# MicroController.net
KiCad netlist of a schematic drawn in Altium Designer
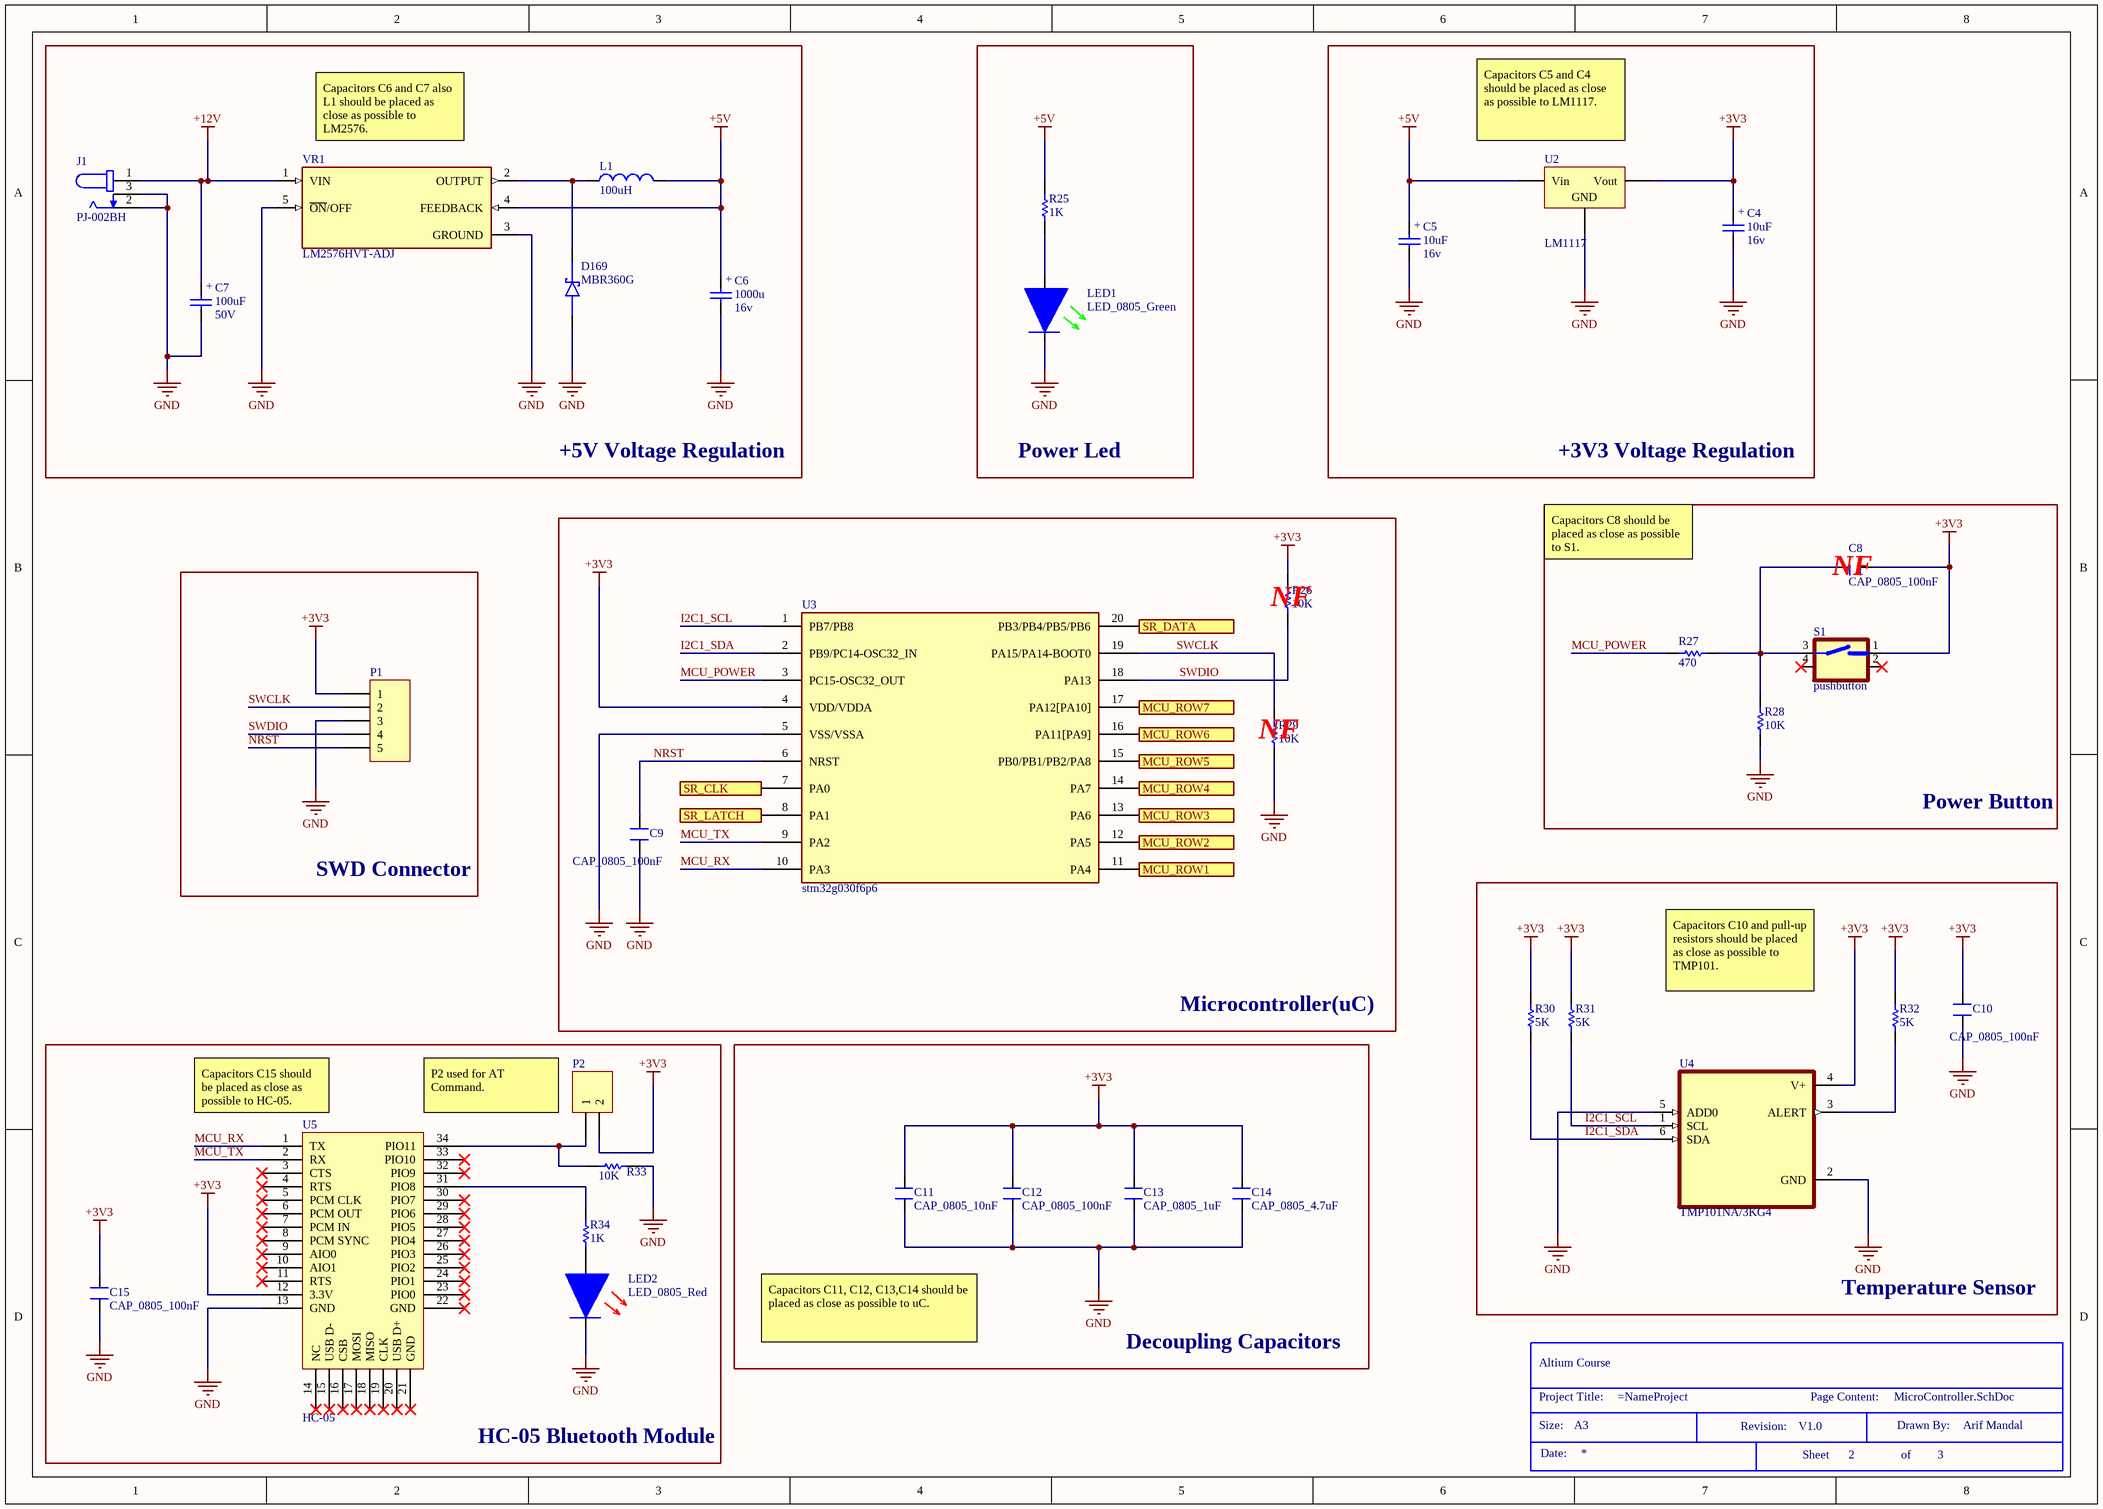
[diagram p0: MicroController.SchDoc]

(export (version "E")
  (design (tool "Eeschema 10.0.6"))
  (components
    (comp (ref "*")
      (value "Title Block")
      (fields (field (name "SIZE") "A3") (field (name "DRAWN BY") "Arif Mandal"))
      (libsource (lib "Bluetooth_Controlled_Led_Matrix_Design") (part "Title Block"))
    )
    (comp (ref "C4")
      (value "10uF")
      (footprint "MY_SMC_B")
      (description "Polar capacitor")
      (fields (field (name "ASID PART NUMBER") "C-AS") (field (name "VOLTE") "16v"))
      (libsource (lib "Mylib") (part "Cap Pol"))
    )
    (comp (ref "C5")
      (value "10uF")
      (footprint "MY_SMC_B")
      (description "Polar capacitor")
      (fields (field (name "ASID PART NUMBER") "C-AS") (field (name "VOLTE") "16v"))
      (libsource (lib "Mylib") (part "Cap Pol"))
    )
    (comp (ref "C6")
      (value "1000u")
      (footprint "MY_CLV_0810")
      (description "Polar capacitor")
      (fields (field (name "ASID PART NUMBER") "C-AS") (field (name "VOLTE") "16v"))
      (libsource (lib "Mylib") (part "Cap Pol"))
    )
    (comp (ref "C7")
      (value "100uF")
      (footprint "MY_CLV_0810")
      (description "Polar capacitor")
      (fields (field (name "ASID PART NUMBER") "C-AS") (field (name "VOLTE") "50V"))
      (libsource (lib "Mylib") (part "Cap Pol"))
    )
    (comp (ref "C8")
      (value "CAP_0805_100nF")
      (footprint "CAP_0805")
      (description "0805 100nF 16VDC ±10% X7R")
      (fields (field (name "TOLERANCE") "%10"))
      (libsource (lib "I2C_Shield") (part "CAP_0805_100nF"))
    )
    (comp (ref "C9")
      (value "CAP_0805_100nF")
      (footprint "CAP_0805")
      (description "0805 100nF 16VDC ±10% X7R")
      (fields (field (name "TOLERANCE") "%10"))
      (libsource (lib "I2C_Shield") (part "CAP_0805_100nF"))
    )
    (comp (ref "C10")
      (value "CAP_0805_100nF")
      (footprint "CAP_0805")
      (description "0805 100nF 16VDC ±10% X7R")
      (fields (field (name "TOLERANCE") "%10"))
      (libsource (lib "I2C_Shield") (part "CAP_0805_100nF"))
    )
    (comp (ref "C11")
      (value "CAP_0805_10nF")
      (footprint "CAP_0805")
      (description "0805 10nF 16VDC ±10% X7R")
      (fields (field (name "TOLERANCE") "%10"))
      (libsource (lib "Bluetooth_Controlled_Led_Matrix_Design") (part "CAP_0805_10nF"))
    )
    (comp (ref "C12")
      (value "CAP_0805_100nF")
      (footprint "CAP_0805")
      (description "0805 100nF 16VDC ±10% X7R")
      (fields (field (name "TOLERANCE") "%10"))
      (libsource (lib "I2C_Shield") (part "CAP_0805_100nF"))
    )
    (comp (ref "C13")
      (value "CAP_0805_1uF")
      (footprint "CAP_0805")
      (description "0805 1uF 16VDC ±10% X7R")
      (fields (field (name "TOLERANCE") "%10"))
      (libsource (lib "Bluetooth_Controlled_Led_Matrix_Design") (part "CAP_0805_1uF"))
    )
    (comp (ref "C14")
      (value "CAP_0805_4.7uF")
      (footprint "CAP_0805")
      (description "0805 4.7uF 16VDC ±10% X7R")
      (fields (field (name "TOLERANCE") "%10"))
      (libsource (lib "Bluetooth_Controlled_Led_Matrix_Design") (part "CAP_0805_4.7uF"))
    )
    (comp (ref "C15")
      (value "CAP_0805_100nF")
      (footprint "CAP_0805")
      (description "0805 100nF 16VDC ±10% X7R")
      (fields (field (name "TOLERANCE") "%10"))
      (libsource (lib "I2C_Shield") (part "CAP_0805_100nF"))
    )
    (comp (ref "D169")
      (value "MBR360G")
      (footprint "DIOAD950W125L840D505")
      (description "Diode Schottky 60V 3A Through Hole DO-201AD")
      (fields (field (name "MF") "ON Semiconductor"))
      (libsource (lib "Bluetooth_Controlled_Led_Matrix_Design") (part "MBR360G"))
    )
    (comp (ref "J1")
      (value "PJ-002BH")
      (footprint "CUI_PJ-002BH")
      (description "2.5 x 6.5 mm, 5.0 A, Horizontal, Through Hole, Dc Power Jack Connector")
      (fields (field (name "MF") "CUI Devices"))
      (libsource (lib "Bluetooth_Controlled_Led_Matrix_Design") (part "PJ-002BH"))
    )
    (comp (ref "L1")
      (value "100uH")
      (footprint "MY_DR125")
      (description "Inductor")
      (fields (field (name "ASID PART NUMBER") "Inductor-AS"))
      (libsource (lib "Mylib") (part "Inductor"))
    )
    (comp (ref "LED1")
      (value "LED_0805_Green")
      (footprint "LED_0805")
      (description "LED SMD 0805 GREEN 550mcd")
      (libsource (lib "I2C_Shield") (part "LED_0805_Green"))
    )
    (comp (ref "LED2")
      (value "LED_0805_Red")
      (footprint "LED_0805")
      (description "LED SMD 0805 RED 550mcd")
      (libsource (lib "I2C_Shield") (part "LED_0805_Red"))
    )
    (comp (ref "P1")
      (value "Header 5")
      (footprint "My_1X05")
      (description "Header, 5-Pin")
      (fields (field (name "ASID PART NUMBER") "Header 5-AS"))
      (libsource (lib "Mylib") (part "Header 5"))
    )
    (comp (ref "P2")
      (value "Header 2")
      (footprint "My_1X02")
      (description "Header, 2-Pin")
      (fields (field (name "ASID PART NUMBER") "Header 2-AS"))
      (libsource (lib "Mylib") (part "Header 2"))
    )
    (comp (ref "R25")
      (value "1K")
      (footprint "MY_0805")
      (description "Standard resistor")
      (fields (field (name "ASID PART NUMBER") "Res-AS"))
      (libsource (lib "Mylib") (part "Res"))
    )
    (comp (ref "R26")
      (value "10K")
      (footprint "MY_0805")
      (description "Standard resistor")
      (fields (field (name "ASID PART NUMBER") "Res-AS"))
      (libsource (lib "Mylib") (part "Res"))
    )
    (comp (ref "R27")
      (value "470")
      (footprint "MY_0805")
      (description "Standard resistor")
      (fields (field (name "ASID PART NUMBER") "Res-AS"))
      (libsource (lib "Mylib") (part "Res"))
    )
    (comp (ref "R28")
      (value "10K")
      (footprint "MY_0805")
      (description "Standard resistor")
      (fields (field (name "ASID PART NUMBER") "Res-AS"))
      (libsource (lib "Mylib") (part "Res"))
    )
    (comp (ref "R29")
      (value "10K")
      (footprint "MY_0805")
      (description "Standard resistor")
      (fields (field (name "ASID PART NUMBER") "Res-AS"))
      (libsource (lib "Mylib") (part "Res"))
    )
    (comp (ref "R30")
      (value "5K")
      (footprint "MY_0805")
      (description "Standard resistor")
      (fields (field (name "ASID PART NUMBER") "Res-AS"))
      (libsource (lib "Mylib") (part "Res"))
    )
    (comp (ref "R31")
      (value "5K")
      (footprint "MY_0805")
      (description "Standard resistor")
      (fields (field (name "ASID PART NUMBER") "Res-AS"))
      (libsource (lib "Mylib") (part "Res"))
    )
    (comp (ref "R32")
      (value "5K")
      (footprint "MY_0805")
      (description "Standard resistor")
      (fields (field (name "ASID PART NUMBER") "Res-AS"))
      (libsource (lib "Mylib") (part "Res"))
    )
    (comp (ref "R33")
      (value "10K")
      (footprint "MY_0805")
      (description "Standard resistor")
      (fields (field (name "ASID PART NUMBER") "Res-AS"))
      (libsource (lib "Mylib") (part "Res"))
    )
    (comp (ref "R34")
      (value "1K")
      (footprint "MY_0805")
      (description "Standard resistor")
      (fields (field (name "ASID PART NUMBER") "Res-AS"))
      (libsource (lib "Mylib") (part "Res"))
    )
    (comp (ref "S1")
      (value "pushbutton")
      (footprint "button")
      (libsource (lib "Bluetooth_Controlled_Led_Matrix_Design") (part "pushbutton"))
    )
    (comp (ref "U2")
      (value "LM1117")
      (footprint "MY_SOT223")
      (description "Low Drop Voltage Reg")
      (fields (field (name "ASID PART NUMBER") "LM1117-AS"))
      (libsource (lib "Mylib") (part "LM1117"))
    )
    (comp (ref "U3")
      (value "stm32g030f6p6")
      (footprint "TSSOP20")
      (description "ARM® Cortex®-M0+ STM32G0 Microcontroller IC 32-Bit Single-Core 64MHz 32KB (32K x 8) FLASH 20-TSSOP")
      (libsource (lib "Bluetooth_Controlled_Led_Matrix_Design") (part "stm32g030f6p6"))
    )
    (comp (ref "U4")
      (value "TMP101NA/3KG4")
      (footprint "SOT95P280X145-6N")
      (libsource (lib "Bluetooth_Controlled_Led_Matrix_Design") (part "TMP101NA/3KG4"))
    )
    (comp (ref "U5")
      (value "HC-05")
      (footprint "HC-05")
      (libsource (lib "Bluetooth_Controlled_Led_Matrix_Design") (part "HC-05"))
    )
    (comp (ref "VR1")
      (value "LM2576HVT-ADJ")
      (footprint "TO170P1067X483X1651-5")
      (description "SIMPLE SWITCHER&reg; 4V to 60V, 3A Low Component Count Step-Down Regulator 5-TO-220 -40 to 125")
      (fields (field (name "MF") "Texas Instruments"))
      (libsource (lib "Bluetooth_Controlled_Led_Matrix_Design") (part "LM2576HVT-ADJ"))
    )
  )
  (nets
    (net (code "1") (name "+3V3") (class "Default")
      (node (ref "C10") (pin "2") (pinfunction "2_2") (pintype "passive"))
      (node (ref "C11") (pin "2") (pinfunction "2_2") (pintype "passive"))
      (node (ref "C12") (pin "2") (pinfunction "2_2") (pintype "passive"))
      (node (ref "C13") (pin "2") (pinfunction "2_2") (pintype "passive"))
      (node (ref "C14") (pin "2") (pinfunction "2_2") (pintype "passive"))
      (node (ref "C15") (pin "2") (pinfunction "2_2") (pintype "passive"))
      (node (ref "C4") (pin "+") (pinfunction "+_+") (pintype "passive"))
      (node (ref "C8") (pin "2") (pinfunction "2_2") (pintype "passive"))
      (node (ref "P1") (pin "1") (pinfunction "1_1") (pintype "passive"))
      (node (ref "P2") (pin "2") (pinfunction "2_2") (pintype "passive"))
      (node (ref "R26") (pin "1") (pinfunction "1_1") (pintype "passive"))
      (node (ref "R30") (pin "1") (pinfunction "1_1") (pintype "passive"))
      (node (ref "R31") (pin "1") (pinfunction "1_1") (pintype "passive"))
      (node (ref "R32") (pin "1") (pinfunction "1_1") (pintype "passive"))
      (node (ref "S1") (pin "1") (pinfunction "2_1") (pintype "passive"))
      (node (ref "U2") (pin "2") (pinfunction "Vout_2") (pintype "passive"))
      (node (ref "U3") (pin "4") (pinfunction "VDD/VDDA_4") (pintype "passive"))
      (node (ref "U4") (pin "4") (pinfunction "V+_4") (pintype "power_in"))
      (node (ref "U5") (pin "12") (pinfunction "3.3V_12") (pintype "passive"))
    )
    (net (code "2") (name "+5V") (class "Default")
      (node (ref "C5") (pin "+") (pinfunction "+_+") (pintype "passive"))
      (node (ref "C6") (pin "+") (pinfunction "+_+") (pintype "passive"))
      (node (ref "L1") (pin "2") (pinfunction "2_2") (pintype "passive"))
      (node (ref "R25") (pin "2") (pinfunction "2_2") (pintype "passive"))
      (node (ref "U2") (pin "3") (pinfunction "Vin_3") (pintype "passive"))
      (node (ref "VR1") (pin "4") (pinfunction "FEEDBACK_4") (pintype "input"))
    )
    (net (code "3") (name "+12V") (class "Default")
      (node (ref "C7") (pin "+") (pinfunction "+_+") (pintype "passive"))
      (node (ref "J1") (pin "1") (pinfunction "1_1") (pintype "passive"))
      (node (ref "VR1") (pin "1") (pinfunction "VIN_1") (pintype "input"))
    )
    (net (code "4") (name "/I2C1_SCL") (class "Default")
      (node (ref "R31") (pin "2") (pinfunction "2_2") (pintype "passive"))
      (node (ref "U3") (pin "1") (pinfunction "PB7/PB8_1") (pintype "passive"))
      (node (ref "U4") (pin "1") (pinfunction "SCL_1") (pintype "input"))
    )
    (net (code "5") (name "/I2C1_SDA") (class "Default")
      (node (ref "R30") (pin "2") (pinfunction "2_2") (pintype "passive"))
      (node (ref "U3") (pin "2") (pinfunction "PB9/PC14-OSC32_IN_2") (pintype "passive"))
      (node (ref "U4") (pin "6") (pinfunction "SDA_6") (pintype "input"))
    )
    (net (code "6") (name "/MCU_POWER") (class "Default")
      (node (ref "R27") (pin "1") (pinfunction "1_1") (pintype "passive"))
      (node (ref "U3") (pin "3") (pinfunction "PC15-OSC32_OUT_3") (pintype "passive"))
    )
    (net (code "7") (name "/MCU_ROW1") (class "Default")
      (node (ref "U3") (pin "11") (pinfunction "PA4_11") (pintype "passive"))
    )
    (net (code "8") (name "/MCU_ROW2") (class "Default")
      (node (ref "U3") (pin "12") (pinfunction "PA5_12") (pintype "passive"))
    )
    (net (code "9") (name "/MCU_ROW3") (class "Default")
      (node (ref "U3") (pin "13") (pinfunction "PA6_13") (pintype "passive"))
    )
    (net (code "10") (name "/MCU_ROW4") (class "Default")
      (node (ref "U3") (pin "14") (pinfunction "PA7_14") (pintype "passive"))
    )
    (net (code "11") (name "/MCU_ROW5") (class "Default")
      (node (ref "U3") (pin "15") (pinfunction "PB0/PB1/PB2/PA8_15") (pintype "passive"))
    )
    (net (code "12") (name "/MCU_ROW6") (class "Default")
      (node (ref "U3") (pin "16") (pinfunction "PA11[PA9]_16") (pintype "passive"))
    )
    (net (code "13") (name "/MCU_ROW7") (class "Default")
      (node (ref "U3") (pin "17") (pinfunction "PA12[PA10]_17") (pintype "passive"))
    )
    (net (code "14") (name "/MCU_RX") (class "Default")
      (node (ref "U3") (pin "10") (pinfunction "PA3_10") (pintype "passive"))
      (node (ref "U5") (pin "1") (pinfunction "TX_1") (pintype "passive"))
    )
    (net (code "15") (name "/MCU_TX") (class "Default")
      (node (ref "U3") (pin "9") (pinfunction "PA2_9") (pintype "passive"))
      (node (ref "U5") (pin "2") (pinfunction "RX_2") (pintype "passive"))
    )
    (net (code "16") (name "/NRST") (class "Default")
      (node (ref "C9") (pin "2") (pinfunction "2_2") (pintype "passive"))
      (node (ref "P1") (pin "5") (pinfunction "5_5") (pintype "passive"))
      (node (ref "U3") (pin "6") (pinfunction "NRST_6") (pintype "passive"))
    )
    (net (code "17") (name "/SR_CLK") (class "Default")
      (node (ref "U3") (pin "7") (pinfunction "PA0_7") (pintype "passive"))
    )
    (net (code "18") (name "/SR_DATA") (class "Default")
      (node (ref "U3") (pin "20") (pinfunction "PB3/PB4/PB5/PB6_20") (pintype "passive"))
    )
    (net (code "19") (name "/SR_LATCH") (class "Default")
      (node (ref "U3") (pin "8") (pinfunction "PA1_8") (pintype "passive"))
    )
    (net (code "20") (name "/SWCLK") (class "Default")
      (node (ref "P1") (pin "2") (pinfunction "2_2") (pintype "passive"))
      (node (ref "R29") (pin "1") (pinfunction "1_1") (pintype "passive"))
      (node (ref "U3") (pin "19") (pinfunction "PA15/PA14-BOOT0_19") (pintype "passive"))
    )
    (net (code "21") (name "/SWDIO") (class "Default")
      (node (ref "P1") (pin "4") (pinfunction "4_4") (pintype "passive"))
      (node (ref "R26") (pin "2") (pinfunction "2_2") (pintype "passive"))
      (node (ref "U3") (pin "18") (pinfunction "PA13_18") (pintype "passive"))
    )
    (net (code "22") (name "GND") (class "Default")
      (node (ref "C10") (pin "1") (pinfunction "1_1") (pintype "passive"))
      (node (ref "C11") (pin "1") (pinfunction "1_1") (pintype "passive"))
      (node (ref "C12") (pin "1") (pinfunction "1_1") (pintype "passive"))
      (node (ref "C13") (pin "1") (pinfunction "1_1") (pintype "passive"))
      (node (ref "C14") (pin "1") (pinfunction "1_1") (pintype "passive"))
      (node (ref "C15") (pin "1") (pinfunction "1_1") (pintype "passive"))
      (node (ref "C4") (pin "-") (pinfunction "-_-") (pintype "passive"))
      (node (ref "C5") (pin "-") (pinfunction "-_-") (pintype "passive"))
      (node (ref "C6") (pin "-") (pinfunction "-_-") (pintype "passive"))
      (node (ref "C7") (pin "-") (pinfunction "-_-") (pintype "passive"))
      (node (ref "C9") (pin "1") (pinfunction "1_1") (pintype "passive"))
      (node (ref "D169") (pin "A") (pinfunction "A_A") (pintype "passive"))
      (node (ref "J1") (pin "2") (pinfunction "2_2") (pintype "passive"))
      (node (ref "J1") (pin "3") (pinfunction "3_3") (pintype "passive"))
      (node (ref "LED1") (pin "C") (pinfunction "C_C") (pintype "passive"))
      (node (ref "LED2") (pin "C") (pinfunction "C_C") (pintype "passive"))
      (node (ref "P1") (pin "3") (pinfunction "3_3") (pintype "passive"))
      (node (ref "R28") (pin "2") (pinfunction "2_2") (pintype "passive"))
      (node (ref "R29") (pin "2") (pinfunction "2_2") (pintype "passive"))
      (node (ref "R33") (pin "1") (pinfunction "1_1") (pintype "passive"))
      (node (ref "U2") (pin "1") (pinfunction "GND_1") (pintype "passive"))
      (node (ref "U3") (pin "5") (pinfunction "VSS/VSSA_5") (pintype "passive"))
      (node (ref "U4") (pin "2") (pinfunction "GND_2") (pintype "power_in"))
      (node (ref "U4") (pin "5") (pinfunction "ADD0_5") (pintype "input"))
      (node (ref "U5") (pin "13") (pinfunction "GND_13") (pintype "passive"))
      (node (ref "VR1") (pin "3") (pinfunction "GROUND_3") (pintype "power_in"))
      (node (ref "VR1") (pin "5") (pinfunction "~{ON}/OFF_5") (pintype "input"))
    )
    (net (code "23") (name "Net-(C8-Pad1)") (class "Default")
      (node (ref "C8") (pin "1") (pinfunction "1_1") (pintype "passive"))
      (node (ref "R27") (pin "2") (pinfunction "2_2") (pintype "passive"))
      (node (ref "R28") (pin "1") (pinfunction "1_1") (pintype "passive"))
      (node (ref "S1") (pin "3") (pinfunction "1_3") (pintype "passive"))
    )
    (net (code "24") (name "Net-(LED1-PadA)") (class "Default")
      (node (ref "LED1") (pin "A") (pinfunction "A_A") (pintype "passive"))
      (node (ref "R25") (pin "1") (pinfunction "1_1") (pintype "passive"))
    )
    (net (code "25") (name "Net-(LED2-PadA)") (class "Default")
      (node (ref "LED2") (pin "A") (pinfunction "A_A") (pintype "passive"))
      (node (ref "R34") (pin "1") (pinfunction "1_1") (pintype "passive"))
    )
    (net (code "26") (name "Net-(U4-ALERT)") (class "Default")
      (node (ref "R32") (pin "2") (pinfunction "2_2") (pintype "passive"))
      (node (ref "U4") (pin "3") (pinfunction "ALERT_3") (pintype "output"))
    )
    (net (code "27") (name "Net-(U5-PIO8)") (class "Default")
      (node (ref "R34") (pin "2") (pinfunction "2_2") (pintype "passive"))
      (node (ref "U5") (pin "31") (pinfunction "PIO8_31") (pintype "passive"))
    )
    (net (code "28") (name "Net-(U5-PIO11)") (class "Default")
      (node (ref "P2") (pin "1") (pinfunction "1_1") (pintype "passive"))
      (node (ref "R33") (pin "2") (pinfunction "2_2") (pintype "passive"))
      (node (ref "U5") (pin "34") (pinfunction "PIO11_34") (pintype "passive"))
    )
    (net (code "29") (name "Net-(VR1-OUTPUT)") (class "Default")
      (node (ref "D169") (pin "C") (pinfunction "C_C") (pintype "passive"))
      (node (ref "L1") (pin "1") (pinfunction "1_1") (pintype "passive"))
      (node (ref "VR1") (pin "2") (pinfunction "OUTPUT_2") (pintype "output"))
    )
    (net (code "30") (name "unconnected-(S1-1-Pad4)") (class "Default")
      (node (ref "S1") (pin "4") (pinfunction "1_4") (pintype "passive+no_connect"))
    )
    (net (code "31") (name "unconnected-(S1-Pad2)") (class "Default")
      (node (ref "S1") (pin "2") (pinfunction "2_2") (pintype "passive+no_connect"))
    )
    (net (code "32") (name "unconnected-(U5-AIO0-Pad9)") (class "Default")
      (node (ref "U5") (pin "9") (pinfunction "AIO0_9") (pintype "passive+no_connect"))
    )
    (net (code "33") (name "unconnected-(U5-AIO1-Pad10)") (class "Default")
      (node (ref "U5") (pin "10") (pinfunction "AIO1_10") (pintype "passive+no_connect"))
    )
    (net (code "34") (name "unconnected-(U5-CLK-Pad19)") (class "Default")
      (node (ref "U5") (pin "19") (pinfunction "CLK_19") (pintype "passive+no_connect"))
    )
    (net (code "35") (name "unconnected-(U5-CSB-Pad16)") (class "Default")
      (node (ref "U5") (pin "16") (pinfunction "CSB_16") (pintype "passive+no_connect"))
    )
    (net (code "36") (name "unconnected-(U5-CTS-Pad3)") (class "Default")
      (node (ref "U5") (pin "3") (pinfunction "CTS_3") (pintype "passive+no_connect"))
    )
    (net (code "37") (name "unconnected-(U5-GND-Pad21)") (class "Default")
      (node (ref "U5") (pin "21") (pinfunction "GND_21") (pintype "passive+no_connect"))
    )
    (net (code "38") (name "unconnected-(U5-GND-Pad22)") (class "Default")
      (node (ref "U5") (pin "22") (pinfunction "GND_22") (pintype "passive+no_connect"))
    )
    (net (code "39") (name "unconnected-(U5-MISO-Pad18)") (class "Default")
      (node (ref "U5") (pin "18") (pinfunction "MISO_18") (pintype "passive+no_connect"))
    )
    (net (code "40") (name "unconnected-(U5-MOSI-Pad17)") (class "Default")
      (node (ref "U5") (pin "17") (pinfunction "MOSI_17") (pintype "passive+no_connect"))
    )
    (net (code "41") (name "unconnected-(U5-NC-Pad14)") (class "Default")
      (node (ref "U5") (pin "14") (pinfunction "NC_14") (pintype "passive+no_connect"))
    )
    (net (code "42") (name "unconnected-(U5-PCM_CLK-Pad5)") (class "Default")
      (node (ref "U5") (pin "5") (pinfunction "PCM_CLK_5") (pintype "passive+no_connect"))
    )
    (net (code "43") (name "unconnected-(U5-PCM_IN-Pad7)") (class "Default")
      (node (ref "U5") (pin "7") (pinfunction "PCM_IN_7") (pintype "passive+no_connect"))
    )
    (net (code "44") (name "unconnected-(U5-PCM_OUT-Pad6)") (class "Default")
      (node (ref "U5") (pin "6") (pinfunction "PCM_OUT_6") (pintype "passive+no_connect"))
    )
    (net (code "45") (name "unconnected-(U5-PCM_SYNC-Pad8)") (class "Default")
      (node (ref "U5") (pin "8") (pinfunction "PCM_SYNC_8") (pintype "passive+no_connect"))
    )
    (net (code "46") (name "unconnected-(U5-PIO0-Pad23)") (class "Default")
      (node (ref "U5") (pin "23") (pinfunction "PIO0_23") (pintype "passive+no_connect"))
    )
    (net (code "47") (name "unconnected-(U5-PIO1-Pad24)") (class "Default")
      (node (ref "U5") (pin "24") (pinfunction "PIO1_24") (pintype "passive+no_connect"))
    )
    (net (code "48") (name "unconnected-(U5-PIO2-Pad25)") (class "Default")
      (node (ref "U5") (pin "25") (pinfunction "PIO2_25") (pintype "passive+no_connect"))
    )
    (net (code "49") (name "unconnected-(U5-PIO3-Pad26)") (class "Default")
      (node (ref "U5") (pin "26") (pinfunction "PIO3_26") (pintype "passive+no_connect"))
    )
    (net (code "50") (name "unconnected-(U5-PIO4-Pad27)") (class "Default")
      (node (ref "U5") (pin "27") (pinfunction "PIO4_27") (pintype "passive+no_connect"))
    )
    (net (code "51") (name "unconnected-(U5-PIO5-Pad28)") (class "Default")
      (node (ref "U5") (pin "28") (pinfunction "PIO5_28") (pintype "passive+no_connect"))
    )
    (net (code "52") (name "unconnected-(U5-PIO6-Pad29)") (class "Default")
      (node (ref "U5") (pin "29") (pinfunction "PIO6_29") (pintype "passive+no_connect"))
    )
    (net (code "53") (name "unconnected-(U5-PIO7-Pad30)") (class "Default")
      (node (ref "U5") (pin "30") (pinfunction "PIO7_30") (pintype "passive+no_connect"))
    )
    (net (code "54") (name "unconnected-(U5-PIO9-Pad32)") (class "Default")
      (node (ref "U5") (pin "32") (pinfunction "PIO9_32") (pintype "passive+no_connect"))
    )
    (net (code "55") (name "unconnected-(U5-PIO10-Pad33)") (class "Default")
      (node (ref "U5") (pin "33") (pinfunction "PIO10_33") (pintype "passive+no_connect"))
    )
    (net (code "56") (name "unconnected-(U5-RTS-Pad4)") (class "Default")
      (node (ref "U5") (pin "4") (pinfunction "RTS_4") (pintype "passive+no_connect"))
    )
    (net (code "57") (name "unconnected-(U5-RTS-Pad11)") (class "Default")
      (node (ref "U5") (pin "11") (pinfunction "RTS_11") (pintype "passive+no_connect"))
    )
    (net (code "58") (name "unconnected-(U5-USB_D+-Pad20)") (class "Default")
      (node (ref "U5") (pin "20") (pinfunction "USB_D+_20") (pintype "passive+no_connect"))
    )
    (net (code "59") (name "unconnected-(U5-USB_D--Pad15)") (class "Default")
      (node (ref "U5") (pin "15") (pinfunction "USB_D-_15") (pintype "passive+no_connect"))
    )
  )
)
